# QCopterRC_POWER_Sch.net
KiCad netlist of a schematic drawn in Altium Designer
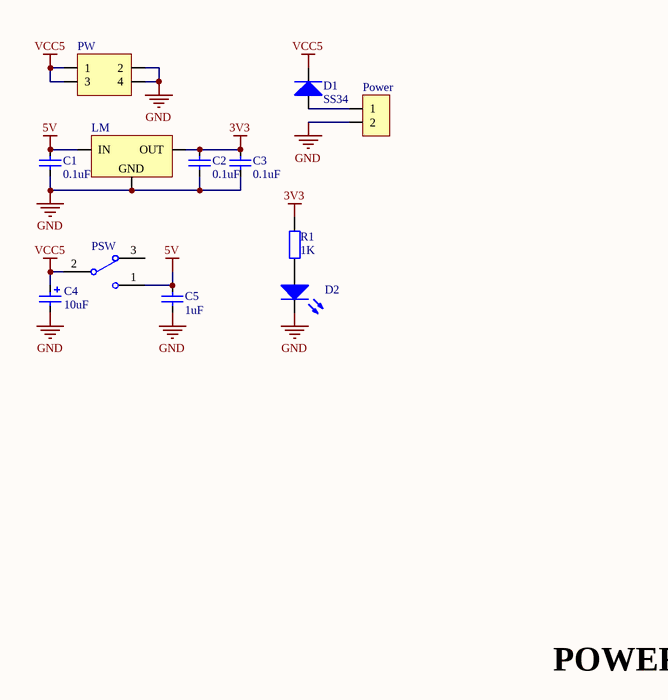
[diagram p0: QCopterRC_POWER_Sch.SchDoc]

(export (version "E")
  (design (tool "Eeschema 10.0.6"))
  (components
    (comp (ref "C1")
      (value "0.1uF")
      (footprint "PCB_Passive:CAP_0603")
      (description "Capacitor")
      (fields (field (name "Comment") "Cap_0603"))
      (libsource (lib "SCH_Passive") (part "Cap_0603"))
    )
    (comp (ref "C2")
      (value "0.1uF")
      (footprint "PCB_Passive:CAP_0603")
      (description "Capacitor")
      (fields (field (name "Comment") "Cap_0603"))
      (libsource (lib "SCH_Passive") (part "Cap_0603"))
    )
    (comp (ref "C3")
      (value "0.1uF")
      (footprint "PCB_Passive:CAP_0603")
      (description "Capacitor")
      (fields (field (name "Comment") "Cap_0603"))
      (libsource (lib "SCH_Passive") (part "Cap_0603"))
    )
    (comp (ref "C4")
      (value "10uF")
      (footprint "PCB_Passive:CAP_TAN_B1210")
      (description "Capacitor")
      (fields (field (name "Comment") "Cap_Tan_1210"))
      (libsource (lib "SCH_Passive") (part "Cap_Tan_1210"))
    )
    (comp (ref "C5")
      (value "1uF")
      (footprint "PCB_Passive:CAP_0603")
      (description "Capacitor")
      (fields (field (name "Comment") "Cap_0603"))
      (libsource (lib "SCH_Passive") (part "Cap_0603"))
    )
    (comp (ref "D1")
      (value "Diode_SMA")
      (footprint "PCB_Active:DO-214AC")
      (description "Diode")
      (fields (field (name "SMA") "SS34"))
      (libsource (lib "SCH_Active") (part "Diode_SMA"))
    )
    (comp (ref "D2")
      (value "LED_0603_WHITE")
      (footprint "PCB_Active:LED_0603_WHITE")
      (description "LED")
      (libsource (lib "SCH_Active") (part "LED_0603_WHITE"))
    )
    (comp (ref "LM")
      (value "LM1117")
      (footprint "PCB_IC:SOT223")
      (description "Power")
      (libsource (lib "SCH_IC") (part "LM1117"))
    )
    (comp (ref "Power")
      (value "HDR1X2_90_2.54")
      (footprint "PCB_Connector:HDR1X2_90_2.54")
      (description "Header")
      (libsource (lib "SCH_Connector") (part "HDR1X2_90_2.54"))
    )
    (comp (ref "PSW")
      (value "SW_SPDT_4.3X8.6_D90")
      (footprint "PCB_Switch:SW_SPDT_4.3X8.6_D90")
      (description "Switch")
      (libsource (lib "SCH_Switch") (part "SW_SPDT_4.3X8.6_D90"))
    )
    (comp (ref "PW")
      (value "HDR2X2_90_2.54")
      (footprint "PCB_Connector:HDR2X2_90_2.54")
      (description "Header")
      (libsource (lib "SCH_Connector") (part "HDR2X2_90_2.54"))
    )
    (comp (ref "R1")
      (value "1K")
      (footprint "PCB_Passive:RES_0603")
      (description "Resistor")
      (fields (field (name "Comment") "Res_0603"))
      (libsource (lib "SCH_Passive") (part "Res_0603"))
    )
  )
  (nets
    (net (code "1") (name "3V3") (class "Default")
      (node (ref "C2") (pin "2") (pinfunction "2_2") (pintype "passive"))
      (node (ref "C3") (pin "2") (pinfunction "2_2") (pintype "passive"))
      (node (ref "LM") (pin "2") (pinfunction "OUT_2") (pintype "power_in"))
      (node (ref "R1") (pin "2") (pinfunction "2_2") (pintype "passive"))
    )
    (net (code "2") (name "5V") (class "Default")
      (node (ref "C1") (pin "1") (pinfunction "1_1") (pintype "passive"))
      (node (ref "C5") (pin "2") (pinfunction "2_2") (pintype "passive"))
      (node (ref "LM") (pin "3") (pinfunction "IN_3") (pintype "power_in"))
      (node (ref "PSW") (pin "1") (pinfunction "1_1") (pintype "passive"))
    )
    (net (code "3") (name "GND") (class "Default")
      (node (ref "C1") (pin "2") (pinfunction "2_2") (pintype "passive"))
      (node (ref "C2") (pin "1") (pinfunction "1_1") (pintype "passive"))
      (node (ref "C3") (pin "1") (pinfunction "1_1") (pintype "passive"))
      (node (ref "C4") (pin "2") (pinfunction "2_2") (pintype "passive"))
      (node (ref "C5") (pin "1") (pinfunction "1_1") (pintype "passive"))
      (node (ref "D2") (pin "2") (pinfunction "K_2") (pintype "passive"))
      (node (ref "LM") (pin "1") (pinfunction "GND_1") (pintype "power_in"))
      (node (ref "PW") (pin "2") (pinfunction "2_2") (pintype "passive"))
      (node (ref "PW") (pin "4") (pinfunction "4_4") (pintype "passive"))
      (node (ref "Power") (pin "2") (pinfunction "2_2") (pintype "passive"))
    )
    (net (code "4") (name "Net-(D1-A)") (class "Default")
      (node (ref "D1") (pin "1") (pinfunction "A_1") (pintype "passive"))
      (node (ref "Power") (pin "1") (pinfunction "1_1") (pintype "passive"))
    )
    (net (code "5") (name "Net-(D2-A)") (class "Default")
      (node (ref "D2") (pin "1") (pinfunction "A_1") (pintype "passive"))
      (node (ref "R1") (pin "1") (pinfunction "1_1") (pintype "passive"))
    )
    (net (code "6") (name "VCC5") (class "Default")
      (node (ref "C4") (pin "1") (pinfunction "1_1") (pintype "passive"))
      (node (ref "D1") (pin "2") (pinfunction "K_2") (pintype "passive"))
      (node (ref "PSW") (pin "2") (pinfunction "2_2") (pintype "passive"))
      (node (ref "PW") (pin "1") (pinfunction "1_1") (pintype "passive"))
      (node (ref "PW") (pin "3") (pinfunction "3_3") (pintype "passive"))
    )
    (net (code "7") (name "unconnected-(PSW-Pad3)") (class "Default")
      (node (ref "PSW") (pin "3") (pinfunction "3_3") (pintype "passive"))
    )
  )
)
